# SCH_-_Inputs_and_Intermediary.net
KiCad netlist of a schematic drawn in Altium Designer
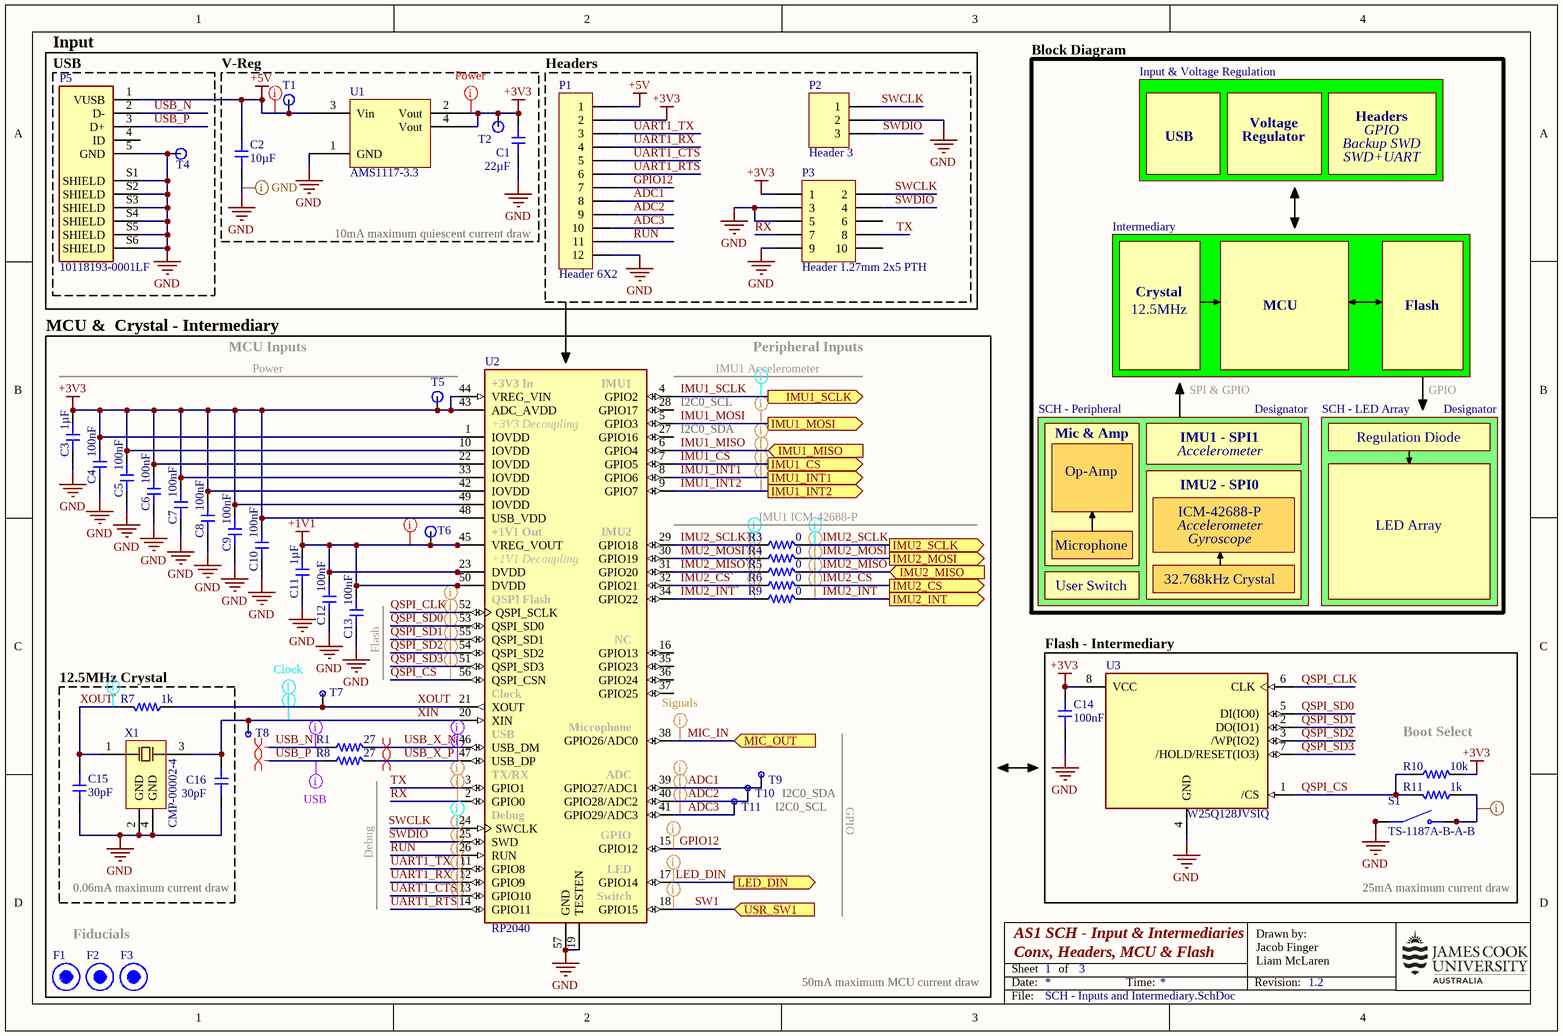
[diagram p0: SCH - Inputs and Intermediary.SchDoc]

(export (version "E")
  (design (tool "Eeschema 10.0.6"))
  (components
    (comp (ref "C1")
      (value "22µF")
      (footprint "CAP-0603")
      (description "Capacitor, Ceramic (MLCC), 22uF, ±20%, 6.3V, X5R, ±20%, SMD 0603")
      (fields
        (field (name "MANUFACTURER PART NUMBER") "CL10A226MQ8NRNC")
        (field (name "JLCPCB BASIC PART") "Yes")
      )
      (libsource (lib "Finmac Systems") (part "GRM21BR61H106KE43L"))
    )
    (comp (ref "C2")
      (value "10µF")
      (footprint "CAP-0402")
      (description "Capacitor, Ceramic (MLCC), 10uF, ±20%, 6.3V, X5R, ±20%, SMD 0402")
      (fields
        (field (name "MANUFACTURER") "Samsung Electro-Mechanics")
        (field (name "JLCPCB PART NUMBER") "C15525")
      )
      (libsource (lib "Finmac Systems") (part "GRM21BR61H106KE43L"))
    )
    (comp (ref "C3")
      (value "1µF")
      (footprint "CAP-0402")
      (description "Capacitor, Ceramic (MLCC), 1uF, ±10%, 25V, X5R, ±10%, SMD 0402")
      (fields
        (field (name "JLCPCB BASIC PART") "Yes")
        (field (name "MANUFACTURER") "Samsung Electro-Mechanics")
      )
      (libsource (lib "Finmac Systems") (part "GRM21BR61H106KE43L"))
    )
    (comp (ref "C4")
      (value "100nF")
      (footprint "CAP-0402")
      (description "Capacitor, Ceramic (MLCC), 100nF, ±10%, 50V, X7R, ±10%, SMD 0402")
      (fields
        (field (name "MANUFACTURER PART NUMBER") "CL05B104KB54PNC")
        (field (name "MANUFACTURER") "Samsung Electro-Mechanics")
      )
      (libsource (lib "Finmac Systems") (part "GRM21BR61H106KE43L"))
    )
    (comp (ref "C5")
      (value "100nF")
      (footprint "CAP-0402")
      (description "Capacitor, Ceramic (MLCC), 100nF, ±10%, 50V, X7R, ±10%, SMD 0402")
      (fields
        (field (name "MANUFACTURER PART NUMBER") "CL05B104KB54PNC")
        (field (name "MANUFACTURER") "Samsung Electro-Mechanics")
      )
      (libsource (lib "Finmac Systems") (part "GRM21BR61H106KE43L"))
    )
    (comp (ref "C6")
      (value "100nF")
      (footprint "CAP-0402")
      (description "Capacitor, Ceramic (MLCC), 100nF, ±10%, 50V, X7R, ±10%, SMD 0402")
      (fields
        (field (name "MANUFACTURER PART NUMBER") "CL05B104KB54PNC")
        (field (name "MANUFACTURER") "Samsung Electro-Mechanics")
      )
      (libsource (lib "Finmac Systems") (part "GRM21BR61H106KE43L"))
    )
    (comp (ref "C7")
      (value "100nF")
      (footprint "CAP-0402")
      (description "Capacitor, Ceramic (MLCC), 100nF, ±10%, 50V, X7R, ±10%, SMD 0402")
      (fields
        (field (name "MANUFACTURER PART NUMBER") "CL05B104KB54PNC")
        (field (name "MANUFACTURER") "Samsung Electro-Mechanics")
      )
      (libsource (lib "Finmac Systems") (part "GRM21BR61H106KE43L"))
    )
    (comp (ref "C8")
      (value "100nF")
      (footprint "CAP-0402")
      (description "Capacitor, Ceramic (MLCC), 100nF, ±10%, 50V, X7R, ±10%, SMD 0402")
      (fields
        (field (name "MANUFACTURER PART NUMBER") "CL05B104KB54PNC")
        (field (name "MANUFACTURER") "Samsung Electro-Mechanics")
      )
      (libsource (lib "Finmac Systems") (part "GRM21BR61H106KE43L"))
    )
    (comp (ref "C9")
      (value "100nF")
      (footprint "CAP-0402")
      (description "Capacitor, Ceramic (MLCC), 100nF, ±10%, 50V, X7R, ±10%, SMD 0402")
      (fields
        (field (name "MANUFACTURER PART NUMBER") "CL05B104KB54PNC")
        (field (name "MANUFACTURER") "Samsung Electro-Mechanics")
      )
      (libsource (lib "Finmac Systems") (part "GRM21BR61H106KE43L"))
    )
    (comp (ref "C10")
      (value "100nF")
      (footprint "CAP-0402")
      (description "Capacitor, Ceramic (MLCC), 100nF, ±10%, 50V, X7R, ±10%, SMD 0402")
      (fields
        (field (name "MANUFACTURER PART NUMBER") "CL05B104KB54PNC")
        (field (name "MANUFACTURER") "Samsung Electro-Mechanics")
      )
      (libsource (lib "Finmac Systems") (part "GRM21BR61H106KE43L"))
    )
    (comp (ref "C11")
      (value "1µF")
      (footprint "CAP-0402")
      (description "Capacitor, Ceramic (MLCC), 1uF, ±10%, 25V, X5R, ±10%, SMD 0402")
      (fields
        (field (name "JLCPCB BASIC PART") "Yes")
        (field (name "MANUFACTURER") "Samsung Electro-Mechanics")
      )
      (libsource (lib "Finmac Systems") (part "GRM21BR61H106KE43L"))
    )
    (comp (ref "C12")
      (value "100nF")
      (footprint "CAP-0402")
      (description "Capacitor, Ceramic (MLCC), 100nF, ±10%, 50V, X7R, ±10%, SMD 0402")
      (fields
        (field (name "MANUFACTURER PART NUMBER") "CL05B104KB54PNC")
        (field (name "MANUFACTURER") "Samsung Electro-Mechanics")
      )
      (libsource (lib "Finmac Systems") (part "GRM21BR61H106KE43L"))
    )
    (comp (ref "C13")
      (value "100nF")
      (footprint "CAP-0402")
      (description "Capacitor, Ceramic (MLCC), 100nF, ±10%, 50V, X7R, ±10%, SMD 0402")
      (fields
        (field (name "MANUFACTURER PART NUMBER") "CL05B104KB54PNC")
        (field (name "MANUFACTURER") "Samsung Electro-Mechanics")
      )
      (libsource (lib "Finmac Systems") (part "GRM21BR61H106KE43L"))
    )
    (comp (ref "C14")
      (value "100nF")
      (footprint "CAP-0402")
      (description "Capacitor, Ceramic (MLCC), 100nF, ±10%, 50V, X7R, ±10%, SMD 0402")
      (fields
        (field (name "MANUFACTURER PART NUMBER") "CL05B104KB54PNC")
        (field (name "MANUFACTURER") "Samsung Electro-Mechanics")
      )
      (libsource (lib "Finmac Systems") (part "GRM21BR61H106KE43L"))
    )
    (comp (ref "C15")
      (value "30pF")
      (footprint "CAP-0603")
      (description "Capacitor, Ceramic (MLCC), 30pF, ±5%, 50V, C0G, ±5%, SMD 0603")
      (fields (field (name "JLCPCB PART NUMBER") "C1658") (field (name "TOLERANCE") "5%"))
      (libsource (lib "Finmac Systems") (part "GRM21BR61H106KE43L"))
    )
    (comp (ref "C16")
      (value "30pF")
      (footprint "CAP-0603")
      (description "Capacitor, Ceramic (MLCC), 30pF, ±5%, 50V, C0G, ±5%, SMD 0603")
      (fields (field (name "JLCPCB PART NUMBER") "C1658") (field (name "TOLERANCE") "5%"))
      (libsource (lib "Finmac Systems") (part "GRM21BR61H106KE43L"))
    )
    (comp (ref "F1")
      (value "Fiducial Pad")
      (footprint "Fiducial")
      (description "1x2mm Fiducial Pad")
      (libsource (lib "DatumPenLibrary") (part "Fiducial"))
    )
    (comp (ref "F2")
      (value "Fiducial Pad")
      (footprint "Fiducial")
      (description "1x2mm Fiducial Pad")
      (libsource (lib "DatumPenLibrary") (part "Fiducial"))
    )
    (comp (ref "F3")
      (value "Fiducial Pad")
      (footprint "Fiducial")
      (description "1x2mm Fiducial Pad")
      (libsource (lib "DatumPenLibrary") (part "Fiducial"))
    )
    (comp (ref "P1")
      (value "Header 6X2")
      (footprint "HDR2X6")
      (description "Header, 6-Pin, Dual row")
      (fields (field (name "PUBLISHER") "Altium Limited"))
      (libsource (lib "SCH_LIB_Assignment1") (part "CMP-002-00136-1"))
    )
    (comp (ref "P2")
      (value "Header 3")
      (footprint "HDR1X3")
      (description "Header, 3-Pin")
      (fields (field (name "PUBLISHER") "Altium Limited"))
      (libsource (lib "James Cook University") (part "Header 3H"))
    )
    (comp (ref "P3")
      (value "Header 1.27mm 2x5 PTH")
      (footprint "Header 1.27mm 2x5 PTH")
      (description "Header 1.27mm pitch, 2x5, PTH through hole")
      (fields (field (name "SOURCE") "JCULibrary.SchLib"))
      (libsource (lib "SCH_LIB_Assignment1") (part "CMP-005-0002-2"))
    )
    (comp (ref "P5")
      (value "10118193-0001LF")
      (footprint "FCI_10118193-0001LF")
      (description "USB - micro B USB 2.0 Receptacle Connector 5 Position Surface Mount, Right Angle; Through Hole")
      (fields (field (name "JLCPCB PART") "C132562") (field (name "MF") "Amphenol ICC"))
      (libsource (lib "SCH_LIB_Assignment1") (part "CMP-045-000000-8"))
    )
    (comp (ref "R1")
      (value "27")
      (footprint "RES-0603")
      (description "Resistor, 27Ω, ±1%, 100mW, 75V, ±200ppm/℃, -55℃~+155℃, SMD 0603")
      (fields (field (name "MANUFACTURER") "Uniroyal") (field (name "JLCPCB PART NUMBER") "C25190"))
      (libsource (lib "Finmac Systems") (part "1206W4F7500T5E"))
    )
    (comp (ref "R3")
      (value "0")
      (footprint "RES-0402")
      (description "Resistor, 0Ω, ±1%, 62.5mW, 50V, ±800ppm/℃, -55℃~+155℃, SMD 0402")
      (fields (field (name "JLCPCB PART NUMBER") "C17168") (field (name "TOLERANCE") "1%"))
      (libsource (lib "Finmac Systems") (part "1206W4F7500T5E"))
    )
    (comp (ref "R4")
      (value "0")
      (footprint "RES-0402")
      (description "Resistor, 0Ω, ±1%, 62.5mW, 50V, ±800ppm/℃, -55℃~+155℃, SMD 0402")
      (fields (field (name "JLCPCB PART NUMBER") "C17168") (field (name "TOLERANCE") "1%"))
      (libsource (lib "Finmac Systems") (part "1206W4F7500T5E"))
    )
    (comp (ref "R5")
      (value "0")
      (footprint "RES-0402")
      (description "Resistor, 0Ω, ±1%, 62.5mW, 50V, ±800ppm/℃, -55℃~+155℃, SMD 0402")
      (fields (field (name "JLCPCB PART NUMBER") "C17168") (field (name "TOLERANCE") "1%"))
      (libsource (lib "Finmac Systems") (part "1206W4F7500T5E"))
    )
    (comp (ref "R6")
      (value "0")
      (footprint "RES-0402")
      (description "Resistor, 0Ω, ±1%, 62.5mW, 50V, ±800ppm/℃, -55℃~+155℃, SMD 0402")
      (fields (field (name "JLCPCB PART NUMBER") "C17168") (field (name "TOLERANCE") "1%"))
      (libsource (lib "Finmac Systems") (part "1206W4F7500T5E"))
    )
    (comp (ref "R7")
      (value "1k")
      (footprint "RES-0402")
      (description "Resistor, 1kΩ, ±1%, 62.5mW, 50V, ±100ppm/℃, -55℃~+155℃, SMD 0402")
      (fields (field (name "JLCPCB PART NUMBER") "C11702") (field (name "JLCPCB BASIC PART") "Yes"))
      (libsource (lib "Finmac Systems") (part "1206W4F7500T5E"))
    )
    (comp (ref "R8")
      (value "27")
      (footprint "RES-0603")
      (description "Resistor, 27Ω, ±1%, 100mW, 75V, ±200ppm/℃, -55℃~+155℃, SMD 0603")
      (fields (field (name "MANUFACTURER") "Uniroyal") (field (name "JLCPCB PART NUMBER") "C25190"))
      (libsource (lib "Finmac Systems") (part "1206W4F7500T5E"))
    )
    (comp (ref "R9")
      (value "0")
      (footprint "RES-0402")
      (description "Resistor, 0Ω, ±1%, 62.5mW, 50V, ±800ppm/℃, -55℃~+155℃, SMD 0402")
      (fields (field (name "JLCPCB PART NUMBER") "C17168") (field (name "TOLERANCE") "1%"))
      (libsource (lib "Finmac Systems") (part "1206W4F7500T5E"))
    )
    (comp (ref "R10")
      (value "10k")
      (footprint "RES-0402")
      (description "Resistor, 10kΩ, ±1%, 62.5mW, 50V, ±100ppm/℃, -55℃~+155℃, SMD 0402")
      (fields (field (name "JLCPCB BASIC PART") "Yes") (field (name "MANUFACTURER") "Uniroyal"))
      (libsource (lib "Finmac Systems") (part "1206W4F7500T5E"))
    )
    (comp (ref "R11")
      (value "1k")
      (footprint "RES-0402")
      (description "Resistor, 1kΩ, ±1%, 62.5mW, 50V, ±100ppm/℃, -55℃~+155℃, SMD 0402")
      (fields (field (name "JLCPCB PART NUMBER") "C11702") (field (name "JLCPCB BASIC PART") "Yes"))
      (libsource (lib "Finmac Systems") (part "1206W4F7500T5E"))
    )
    (comp (ref "S1")
      (value "TS-1187A-B-A-B")
      (footprint "SW_TS-1187A-B-A-B")
      (description "SPST 50mA @ 12VDC Top Actuated Round Button 160gf SMD Tactile Switches RoHS")
      (fields (field (name "JLCPCB PART") "C318884"))
      (libsource (lib "Finmac Systems") (part "CMP-051-000000-5"))
    )
    (comp (ref "T1")
      (value "TP")
      (footprint "TestPoint")
      (libsource (lib "DatumPenLibrary") (part "TestPoint"))
    )
    (comp (ref "T2")
      (value "TP")
      (footprint "TestPoint")
      (libsource (lib "DatumPenLibrary") (part "TestPoint"))
    )
    (comp (ref "T4")
      (value "TP")
      (footprint "TestPoint")
      (libsource (lib "DatumPenLibrary") (part "TestPoint"))
    )
    (comp (ref "T5")
      (value "TP")
      (footprint "TestPoint")
      (libsource (lib "DatumPenLibrary") (part "TestPoint"))
    )
    (comp (ref "T6")
      (value "TP")
      (footprint "TestPoint")
      (libsource (lib "DatumPenLibrary") (part "TestPoint"))
    )
    (comp (ref "T7")
      (value "TP")
      (footprint "TestPoint - Small")
      (libsource (lib "DatumPenLibrary") (part "TestPoint Small"))
    )
    (comp (ref "T8")
      (value "TP")
      (footprint "TestPoint - Small")
      (libsource (lib "DatumPenLibrary") (part "TestPoint Small"))
    )
    (comp (ref "T9")
      (value "TP")
      (footprint "TestPoint - Small")
      (libsource (lib "DatumPenLibrary") (part "TestPoint Small"))
    )
    (comp (ref "T10")
      (value "TP")
      (footprint "TestPoint - Small")
      (libsource (lib "DatumPenLibrary") (part "TestPoint Small"))
    )
    (comp (ref "T11")
      (value "TP")
      (footprint "TestPoint - Small")
      (libsource (lib "DatumPenLibrary") (part "TestPoint Small"))
    )
    (comp (ref "U1")
      (value "AMS1117-3.3")
      (footprint "SOT230P700X180-4N")
      (description "3.3V 1A LOW DROPOUT VOLTAGE REGULATOR SOT-223")
      (fields (field (name "JLCPCB PART") "C6186"))
      (libsource (lib "SCH_LIB_Assignment1") (part "CMP-00001-4"))
    )
    (comp (ref "U2")
      (value "RP2040")
      (footprint "QFN40P700X700X90-57N")
      (description "ARM Cortex-M0+ MCU 32-Bit Microcontroller for Raspberry Pi Pico")
      (fields (field (name "JLCPCB PART") "C2040"))
      (libsource (lib "SCH_LIB_Assignment1") (part "CMP-043-000000-5"))
    )
    (comp (ref "U3")
      (value "W25Q128JVSIQ")
      (footprint "SOIC127P790X216-8N")
      (description "FLASH - NOR Memory IC 128Mb (16M x 8) SPI - Quad I/O, QPI, DTR 133 MHz 8-SOIC")
      (fields (field (name "JLCPCB PART") "C97521") (field (name "MF") "Winbond Electronics"))
      (libsource (lib "SCH_LIB_Assignment1") (part "CMP-031-00006-4"))
    )
    (comp (ref "X1")
      (value "CMP-00002-4")
      (footprint "X322512MSB4SI-Footprint-1")
      (description "12MHz SMD Crystal Resonator 20pF ±10ppm ±30ppm -40℃~+85℃ SMD3225-4P  Crystals ROHS Yangxing Tech")
      (fields (field (name "JLCPCB PART") "C9002"))
      (libsource (lib "Finmac Systems") (part "CMP-00002-4"))
    )
  )
  (nets
    (net (code "1") (name "+1V1") (class "Default")
      (node (ref "C11") (pin "1") (pinfunction "1_1") (pintype "passive"))
      (node (ref "C12") (pin "2") (pinfunction "2_2") (pintype "passive"))
      (node (ref "C13") (pin "2") (pinfunction "2_2") (pintype "passive"))
      (node (ref "T6") (pin "1") (pinfunction "TP_1") (pintype "passive"))
      (node (ref "U2") (pin "23") (pinfunction "DVDD_23") (pintype "power_in"))
      (node (ref "U2") (pin "45") (pinfunction "VREG_VOUT_45") (pintype "power_in"))
      (node (ref "U2") (pin "50") (pinfunction "DVDD_50") (pintype "power_in"))
    )
    (net (code "2") (name "+3V3") (class "Default")
      (node (ref "C1") (pin "2") (pinfunction "2_2") (pintype "passive"))
      (node (ref "C10") (pin "2") (pinfunction "2_2") (pintype "passive"))
      (node (ref "C14") (pin "2") (pinfunction "2_2") (pintype "passive"))
      (node (ref "C3") (pin "2") (pinfunction "2_2") (pintype "passive"))
      (node (ref "C4") (pin "2") (pinfunction "2_2") (pintype "passive"))
      (node (ref "C5") (pin "2") (pinfunction "2_2") (pintype "passive"))
      (node (ref "C6") (pin "2") (pinfunction "2_2") (pintype "passive"))
      (node (ref "C7") (pin "2") (pinfunction "2_2") (pintype "passive"))
      (node (ref "C8") (pin "2") (pinfunction "2_2") (pintype "passive"))
      (node (ref "C9") (pin "2") (pinfunction "2_2") (pintype "passive"))
      (node (ref "P1") (pin "2") (pinfunction "2_2") (pintype "passive"))
      (node (ref "P3") (pin "1") (pinfunction "1_1") (pintype "passive"))
      (node (ref "R10") (pin "2") (pinfunction "2_2") (pintype "passive"))
      (node (ref "T2") (pin "1") (pinfunction "TP_1") (pintype "passive"))
      (node (ref "T5") (pin "1") (pinfunction "TP_1") (pintype "passive"))
      (node (ref "U1") (pin "2") (pinfunction "Vout_2") (pintype "power_in"))
      (node (ref "U1") (pin "4") (pinfunction "Vout_4") (pintype "power_in"))
      (node (ref "U2") (pin "1") (pinfunction "IOVDD_1") (pintype "power_in"))
      (node (ref "U2") (pin "10") (pinfunction "IOVDD_10") (pintype "power_in"))
      (node (ref "U2") (pin "22") (pinfunction "IOVDD_22") (pintype "power_in"))
      (node (ref "U2") (pin "33") (pinfunction "IOVDD_33") (pintype "power_in"))
      (node (ref "U2") (pin "42") (pinfunction "IOVDD_42") (pintype "power_in"))
      (node (ref "U2") (pin "43") (pinfunction "ADC_AVDD_43") (pintype "power_in"))
      (node (ref "U2") (pin "44") (pinfunction "VREG_VIN_44") (pintype "input"))
      (node (ref "U2") (pin "48") (pinfunction "USB_VDD_48") (pintype "power_in"))
      (node (ref "U2") (pin "49") (pinfunction "IOVDD_49") (pintype "power_in"))
      (node (ref "U3") (pin "8") (pinfunction "VCC_8") (pintype "power_in"))
    )
    (net (code "3") (name "+5V") (class "Default")
      (node (ref "C2") (pin "2") (pinfunction "2_2") (pintype "passive"))
      (node (ref "P1") (pin "1") (pinfunction "1_1") (pintype "passive"))
      (node (ref "P5") (pin "1") (pinfunction "VUSB_1") (pintype "passive"))
      (node (ref "T1") (pin "1") (pinfunction "TP_1") (pintype "passive"))
      (node (ref "U1") (pin "3") (pinfunction "Vin_3") (pintype "power_in"))
    )
    (net (code "4") (name "/ADC1") (class "Default")
      (node (ref "P1") (pin "8") (pinfunction "8_8") (pintype "passive"))
      (node (ref "T9") (pin "1") (pinfunction "TP_1") (pintype "passive"))
      (node (ref "U2") (pin "39") (pinfunction "GPIO27/ADC1_39") (pintype "bidirectional"))
    )
    (net (code "5") (name "/ADC2") (class "Default")
      (node (ref "P1") (pin "9") (pinfunction "9_9") (pintype "passive"))
      (node (ref "T10") (pin "1") (pinfunction "TP_1") (pintype "passive"))
      (node (ref "U2") (pin "40") (pinfunction "GPIO28/ADC2_40") (pintype "bidirectional"))
    )
    (net (code "6") (name "/ADC3") (class "Default")
      (node (ref "P1") (pin "10") (pinfunction "10_10") (pintype "passive"))
      (node (ref "T11") (pin "1") (pinfunction "TP_1") (pintype "passive"))
      (node (ref "U2") (pin "41") (pinfunction "GPIO29/ADC3_41") (pintype "bidirectional"))
    )
    (net (code "7") (name "/GPIO12") (class "Default")
      (node (ref "P1") (pin "7") (pinfunction "7_7") (pintype "passive"))
      (node (ref "U2") (pin "15") (pinfunction "GPIO12_15") (pintype "bidirectional"))
    )
    (net (code "8") (name "/IMU1_CS") (class "Default")
      (node (ref "U2") (pin "7") (pinfunction "GPIO5_7") (pintype "bidirectional"))
    )
    (net (code "9") (name "/IMU1_INT1") (class "Default")
      (node (ref "U2") (pin "8") (pinfunction "GPIO6_8") (pintype "bidirectional"))
    )
    (net (code "10") (name "/IMU1_INT2") (class "Default")
      (node (ref "U2") (pin "9") (pinfunction "GPIO7_9") (pintype "bidirectional"))
    )
    (net (code "11") (name "/IMU1_MISO") (class "Default")
      (node (ref "U2") (pin "6") (pinfunction "GPIO4_6") (pintype "bidirectional"))
    )
    (net (code "12") (name "/IMU1_MOSI") (class "Default")
      (node (ref "U2") (pin "5") (pinfunction "GPIO3_5") (pintype "bidirectional"))
    )
    (net (code "13") (name "/IMU1_SCLK") (class "Default")
      (node (ref "U2") (pin "4") (pinfunction "GPIO2_4") (pintype "bidirectional"))
    )
    (net (code "14") (name "/IMU2_CS") (class "Default")
      (node (ref "R6") (pin "2") (pinfunction "2_2") (pintype "passive"))
    )
    (net (code "15") (name "/IMU2_CS`") (class "Default")
      (node (ref "R6") (pin "1") (pinfunction "1_1") (pintype "passive"))
      (node (ref "U2") (pin "32") (pinfunction "GPIO21_32") (pintype "bidirectional"))
    )
    (net (code "16") (name "/IMU2_INT") (class "Default")
      (node (ref "R9") (pin "2") (pinfunction "2_2") (pintype "passive"))
    )
    (net (code "17") (name "/IMU2_INT`") (class "Default")
      (node (ref "R9") (pin "1") (pinfunction "1_1") (pintype "passive"))
      (node (ref "U2") (pin "34") (pinfunction "GPIO22_34") (pintype "bidirectional"))
    )
    (net (code "18") (name "/IMU2_MISO") (class "Default")
      (node (ref "R5") (pin "2") (pinfunction "2_2") (pintype "passive"))
    )
    (net (code "19") (name "/IMU2_MISO`") (class "Default")
      (node (ref "R5") (pin "1") (pinfunction "1_1") (pintype "passive"))
      (node (ref "U2") (pin "31") (pinfunction "GPIO20_31") (pintype "bidirectional"))
    )
    (net (code "20") (name "/IMU2_MOSI") (class "Default")
      (node (ref "R4") (pin "2") (pinfunction "2_2") (pintype "passive"))
    )
    (net (code "21") (name "/IMU2_MOSI`") (class "Default")
      (node (ref "R4") (pin "1") (pinfunction "1_1") (pintype "passive"))
      (node (ref "U2") (pin "30") (pinfunction "GPIO19_30") (pintype "bidirectional"))
    )
    (net (code "22") (name "/IMU2_SCLK") (class "Default")
      (node (ref "R3") (pin "2") (pinfunction "2_2") (pintype "passive"))
    )
    (net (code "23") (name "/IMU2_SCLK`") (class "Default")
      (node (ref "R3") (pin "1") (pinfunction "1_1") (pintype "passive"))
      (node (ref "U2") (pin "29") (pinfunction "GPIO18_29") (pintype "bidirectional"))
    )
    (net (code "24") (name "/LED_DIN") (class "Default")
      (node (ref "U2") (pin "17") (pinfunction "GPIO14_17") (pintype "bidirectional"))
    )
    (net (code "25") (name "/MIC_IN") (class "Default")
      (node (ref "U2") (pin "38") (pinfunction "GPIO26/ADC0_38") (pintype "bidirectional"))
    )
    (net (code "26") (name "/QSPI_CLK") (class "Default")
      (node (ref "U2") (pin "52") (pinfunction "QSPI_SCLK_52") (pintype "bidirectional"))
      (node (ref "U3") (pin "6") (pinfunction "CLK_6") (pintype "input"))
    )
    (net (code "27") (name "/QSPI_CS") (class "Default")
      (node (ref "R10") (pin "1") (pinfunction "1_1") (pintype "passive"))
      (node (ref "R11") (pin "2") (pinfunction "2_2") (pintype "passive"))
      (node (ref "U2") (pin "56") (pinfunction "QSPI_CSN_56") (pintype "bidirectional"))
      (node (ref "U3") (pin "1") (pinfunction "/CS_1") (pintype "input"))
    )
    (net (code "28") (name "/QSPI_SD0") (class "Default")
      (node (ref "U2") (pin "53") (pinfunction "QSPI_SD0_53") (pintype "bidirectional"))
      (node (ref "U3") (pin "5") (pinfunction "DI(IO0)_5") (pintype "bidirectional"))
    )
    (net (code "29") (name "/QSPI_SD1") (class "Default")
      (node (ref "U2") (pin "55") (pinfunction "QSPI_SD1_55") (pintype "bidirectional"))
      (node (ref "U3") (pin "2") (pinfunction "DO(IO1)_2") (pintype "bidirectional"))
    )
    (net (code "30") (name "/QSPI_SD2") (class "Default")
      (node (ref "U2") (pin "54") (pinfunction "QSPI_SD2_54") (pintype "bidirectional"))
      (node (ref "U3") (pin "3") (pinfunction "/WP(IO2)_3") (pintype "bidirectional"))
    )
    (net (code "31") (name "/QSPI_SD3") (class "Default")
      (node (ref "U2") (pin "51") (pinfunction "QSPI_SD3_51") (pintype "bidirectional"))
      (node (ref "U3") (pin "7") (pinfunction "/HOLD/RESET(IO3)_7") (pintype "bidirectional"))
    )
    (net (code "32") (name "/RUN") (class "Default")
      (node (ref "P1") (pin "11") (pinfunction "11_11") (pintype "passive"))
      (node (ref "U2") (pin "26") (pinfunction "RUN_26") (pintype "input"))
    )
    (net (code "33") (name "/RX") (class "Default")
      (node (ref "P3") (pin "7") (pinfunction "7_7") (pintype "passive"))
      (node (ref "U2") (pin "2") (pinfunction "GPIO0_2") (pintype "bidirectional"))
    )
    (net (code "34") (name "/SW1") (class "Default")
      (node (ref "U2") (pin "18") (pinfunction "GPIO15_18") (pintype "bidirectional"))
    )
    (net (code "35") (name "/SWCLK") (class "Default")
      (node (ref "P2") (pin "1") (pinfunction "1_1") (pintype "passive"))
      (node (ref "P3") (pin "2") (pinfunction "2_2") (pintype "passive"))
      (node (ref "U2") (pin "24") (pinfunction "SWCLK_24") (pintype "input"))
    )
    (net (code "36") (name "/SWDIO") (class "Default")
      (node (ref "P2") (pin "3") (pinfunction "3_3") (pintype "passive"))
      (node (ref "P3") (pin "4") (pinfunction "4_4") (pintype "passive"))
      (node (ref "U2") (pin "25") (pinfunction "SWD_25") (pintype "bidirectional"))
    )
    (net (code "37") (name "/TX") (class "Default")
      (node (ref "P3") (pin "8") (pinfunction "8_8") (pintype "passive"))
      (node (ref "U2") (pin "3") (pinfunction "GPIO1_3") (pintype "bidirectional"))
    )
    (net (code "38") (name "/UART1_CTS") (class "Default")
      (node (ref "P1") (pin "5") (pinfunction "5_5") (pintype "passive"))
      (node (ref "U2") (pin "13") (pinfunction "GPIO10_13") (pintype "bidirectional"))
    )
    (net (code "39") (name "/UART1_RTS") (class "Default")
      (node (ref "P1") (pin "6") (pinfunction "6_6") (pintype "passive"))
      (node (ref "U2") (pin "14") (pinfunction "GPIO11_14") (pintype "bidirectional"))
    )
    (net (code "40") (name "/UART1_RX") (class "Default")
      (node (ref "P1") (pin "4") (pinfunction "4_4") (pintype "passive"))
      (node (ref "U2") (pin "12") (pinfunction "GPIO9_12") (pintype "bidirectional"))
    )
    (net (code "41") (name "/UART1_TX") (class "Default")
      (node (ref "P1") (pin "3") (pinfunction "3_3") (pintype "passive"))
      (node (ref "U2") (pin "11") (pinfunction "GPIO8_11") (pintype "bidirectional"))
    )
    (net (code "42") (name "/USB_N") (class "Default")
      (node (ref "P5") (pin "2") (pinfunction "D-_2") (pintype "passive"))
      (node (ref "R1") (pin "1") (pinfunction "1_1") (pintype "passive"))
    )
    (net (code "43") (name "/USB_P") (class "Default")
      (node (ref "P5") (pin "3") (pinfunction "D+_3") (pintype "passive"))
      (node (ref "R8") (pin "1") (pinfunction "1_1") (pintype "passive"))
    )
    (net (code "44") (name "/USB_X_N") (class "Default")
      (node (ref "R1") (pin "2") (pinfunction "2_2") (pintype "passive"))
      (node (ref "U2") (pin "46") (pinfunction "USB_DM_46") (pintype "bidirectional"))
    )
    (net (code "45") (name "/USB_X_P") (class "Default")
      (node (ref "R8") (pin "2") (pinfunction "2_2") (pintype "passive"))
      (node (ref "U2") (pin "47") (pinfunction "USB_DP_47") (pintype "bidirectional"))
    )
    (net (code "46") (name "/XIN") (class "Default")
      (node (ref "C16") (pin "2") (pinfunction "2_2") (pintype "passive"))
      (node (ref "T8") (pin "1") (pinfunction "TP_1") (pintype "passive"))
      (node (ref "U2") (pin "20") (pinfunction "XIN_20") (pintype "input"))
      (node (ref "X1") (pin "3") (pinfunction "OSC2_3") (pintype "passive"))
    )
    (net (code "47") (name "/XOUT") (class "Default")
      (node (ref "R7") (pin "1") (pinfunction "1_1") (pintype "passive"))
      (node (ref "T7") (pin "1") (pinfunction "TP_1") (pintype "passive"))
      (node (ref "U2") (pin "21") (pinfunction "XOUT_21") (pintype "output"))
    )
    (net (code "48") (name "/XOUT`") (class "Default")
      (node (ref "C15") (pin "2") (pinfunction "2_2") (pintype "passive"))
      (node (ref "R7") (pin "2") (pinfunction "2_2") (pintype "passive"))
      (node (ref "X1") (pin "1") (pinfunction "OSC1_1") (pintype "passive"))
    )
    (net (code "49") (name "GND") (class "Default")
      (node (ref "C1") (pin "1") (pinfunction "1_1") (pintype "passive"))
      (node (ref "C10") (pin "1") (pinfunction "1_1") (pintype "passive"))
      (node (ref "C11") (pin "2") (pinfunction "2_2") (pintype "passive"))
      (node (ref "C12") (pin "1") (pinfunction "1_1") (pintype "passive"))
      (node (ref "C13") (pin "1") (pinfunction "1_1") (pintype "passive"))
      (node (ref "C14") (pin "1") (pinfunction "1_1") (pintype "passive"))
      (node (ref "C15") (pin "1") (pinfunction "1_1") (pintype "passive"))
      (node (ref "C16") (pin "1") (pinfunction "1_1") (pintype "passive"))
      (node (ref "C2") (pin "1") (pinfunction "1_1") (pintype "passive"))
      (node (ref "C3") (pin "1") (pinfunction "1_1") (pintype "passive"))
      (node (ref "C4") (pin "1") (pinfunction "1_1") (pintype "passive"))
      (node (ref "C5") (pin "1") (pinfunction "1_1") (pintype "passive"))
      (node (ref "C6") (pin "1") (pinfunction "1_1") (pintype "passive"))
      (node (ref "C7") (pin "1") (pinfunction "1_1") (pintype "passive"))
      (node (ref "C8") (pin "1") (pinfunction "1_1") (pintype "passive"))
      (node (ref "C9") (pin "1") (pinfunction "1_1") (pintype "passive"))
      (node (ref "P1") (pin "12") (pinfunction "12_12") (pintype "passive"))
      (node (ref "P2") (pin "2") (pinfunction "2_2") (pintype "passive"))
      (node (ref "P3") (pin "3") (pinfunction "3_3") (pintype "passive"))
      (node (ref "P3") (pin "5") (pinfunction "5_5") (pintype "passive"))
      (node (ref "P3") (pin "9") (pinfunction "9_9") (pintype "passive"))
      (node (ref "P5") (pin "5") (pinfunction "GND_5") (pintype "passive"))
      (node (ref "P5") (pin "S1") (pinfunction "SHIELD_S1") (pintype "passive"))
      (node (ref "P5") (pin "S2") (pinfunction "SHIELD_S2") (pintype "passive"))
      (node (ref "P5") (pin "S3") (pinfunction "SHIELD_S3") (pintype "passive"))
      (node (ref "P5") (pin "S4") (pinfunction "SHIELD_S4") (pintype "passive"))
      (node (ref "P5") (pin "S5") (pinfunction "SHIELD_S5") (pintype "passive"))
      (node (ref "P5") (pin "S6") (pinfunction "SHIELD_S6") (pintype "passive"))
      (node (ref "S1") (pin "A") (pinfunction "COM_A") (pintype "passive"))
      (node (ref "S1") (pin "B") (pinfunction "COM_B") (pintype "passive"))
      (node (ref "T4") (pin "1") (pinfunction "TP_1") (pintype "passive"))
      (node (ref "U1") (pin "1") (pinfunction "GND_1") (pintype "power_in"))
      (node (ref "U2") (pin "19") (pinfunction "TESTEN_19") (pintype "passive"))
      (node (ref "U2") (pin "57") (pinfunction "GND_57") (pintype "power_in"))
      (node (ref "U3") (pin "4") (pinfunction "GND_4") (pintype "power_in"))
      (node (ref "X1") (pin "2") (pinfunction "GND_2") (pintype "passive"))
      (node (ref "X1") (pin "4") (pinfunction "GND_4") (pintype "passive"))
    )
    (net (code "50") (name "Net-(R11-Pad1)") (class "Default")
      (node (ref "R11") (pin "1") (pinfunction "1_1") (pintype "passive"))
      (node (ref "S1") (pin "C") (pinfunction "NO_C") (pintype "passive"))
      (node (ref "S1") (pin "D") (pinfunction "NO_D") (pintype "passive"))
    )
    (net (code "51") (name "unconnected-(P3-Pad6)") (class "Default")
      (node (ref "P3") (pin "6") (pinfunction "6_6") (pintype "passive"))
    )
    (net (code "52") (name "unconnected-(P3-Pad10)") (class "Default")
      (node (ref "P3") (pin "10") (pinfunction "10_10") (pintype "passive"))
    )
    (net (code "53") (name "unconnected-(P5-ID-Pad4)") (class "Default")
      (node (ref "P5") (pin "4") (pinfunction "ID_4") (pintype "passive"))
    )
    (net (code "54") (name "unconnected-(U2-GPIO13-Pad16)") (class "Default")
      (node (ref "U2") (pin "16") (pinfunction "GPIO13_16") (pintype "bidirectional"))
    )
    (net (code "55") (name "unconnected-(U2-GPIO16-Pad27)") (class "Default")
      (node (ref "U2") (pin "27") (pinfunction "GPIO16_27") (pintype "bidirectional"))
    )
    (net (code "56") (name "unconnected-(U2-GPIO17-Pad28)") (class "Default")
      (node (ref "U2") (pin "28") (pinfunction "GPIO17_28") (pintype "bidirectional"))
    )
    (net (code "57") (name "unconnected-(U2-GPIO23-Pad35)") (class "Default")
      (node (ref "U2") (pin "35") (pinfunction "GPIO23_35") (pintype "bidirectional"))
    )
    (net (code "58") (name "unconnected-(U2-GPIO24-Pad36)") (class "Default")
      (node (ref "U2") (pin "36") (pinfunction "GPIO24_36") (pintype "bidirectional"))
    )
    (net (code "59") (name "unconnected-(U2-GPIO25-Pad37)") (class "Default")
      (node (ref "U2") (pin "37") (pinfunction "GPIO25_37") (pintype "bidirectional"))
    )
  )
)
